# Lipo_Charger_Basic.net
KiCad netlist of a schematic drawn in EAGLE
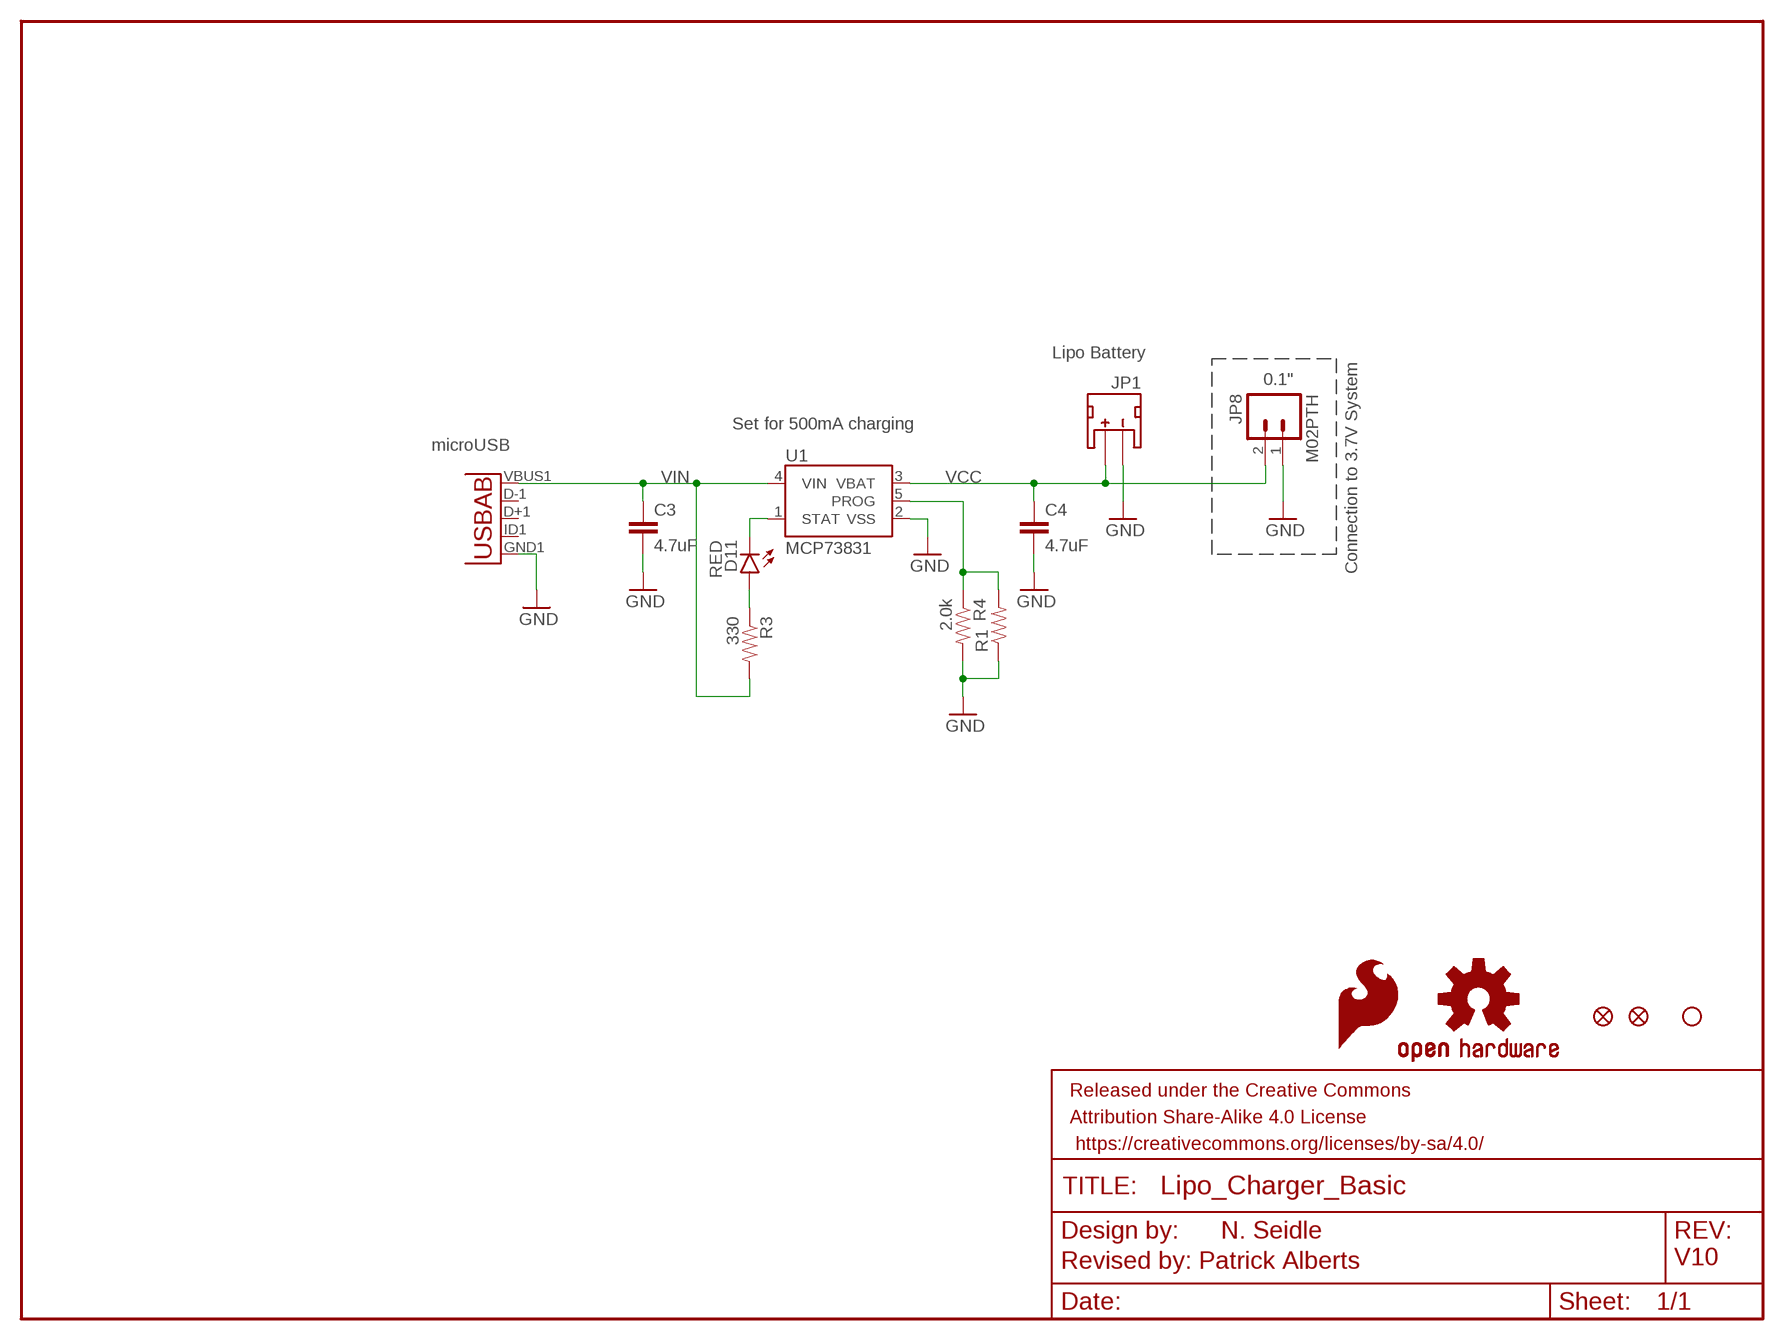
[diagram p0: schematic, sheet 1]

(export (version "E")
  (design (tool "Eeschema 10.0.6"))
  (components
    (comp (ref "C3")
      (value "4.7uF")
      (footprint "eagle-import:0603-CAP")
      (libsource (lib "eagle-import") (part "4.7UF-6.3V-10%(0603)0603"))
    )
    (comp (ref "C4")
      (value "4.7uF")
      (footprint "eagle-import:0603-CAP")
      (libsource (lib "eagle-import") (part "4.7UF-6.3V-10%(0603)0603"))
    )
    (comp (ref "D11")
      (value "RED")
      (footprint "eagle-import:LED-0603")
      (libsource (lib "eagle-import") (part "LED-RED0603"))
    )
    (comp (ref "FRAME1")
      (value "FRAME-LETTER")
      (footprint "eagle-import:CREATIVE_COMMONS")
      (libsource (lib "eagle-import") (part "FRAME-LETTER"))
    )
    (comp (ref "JP1")
      (value "JST")
      (footprint "eagle-import:JST-2-SMD")
      (libsource (lib "eagle-import") (part "JST_2MM_MALE"))
    )
    (comp (ref "JP2")
      (value "STAND-OFF")
      (footprint "eagle-import:STAND-OFF")
      (libsource (lib "eagle-import") (part "STAND-OFF"))
    )
    (comp (ref "JP3")
      (value "FIDUCIAL1X2")
      (footprint "eagle-import:FIDUCIAL-1X2")
      (libsource (lib "eagle-import") (part "FIDUCIAL1X2"))
    )
    (comp (ref "JP4")
      (value "FIDUCIAL1X2")
      (footprint "eagle-import:FIDUCIAL-1X2")
      (libsource (lib "eagle-import") (part "FIDUCIAL1X2"))
    )
    (comp (ref "JP8")
      (value "M02PTH")
      (footprint "eagle-import:1X02")
      (libsource (lib "eagle-import") (part "M02PTH"))
    )
    (comp (ref "JP9")
      (value "Micro USB")
      (footprint "eagle-import:USB-AB-MICRO-SMD_V03")
      (libsource (lib "eagle-import") (part "USB-ABCONN-11794"))
    )
    (comp (ref "LOGO1")
      (value "OSHW-LOGOS")
      (footprint "eagle-import:OSHW-LOGO-S")
      (libsource (lib "eagle-import") (part "OSHW-LOGOS"))
    )
    (comp (ref "LOGO2")
      (value "SFE_LOGO_FLAME.1_INCH")
      (footprint "eagle-import:SFE_LOGO_FLAME_.1")
      (libsource (lib "eagle-import") (part "SFE_LOGO_FLAME.1_INCH"))
    )
    (comp (ref "R1")
      (value "RESISTORPTH-1/4W-VERT-KIT")
      (footprint "eagle-import:AXIAL-0.1EZ")
      (libsource (lib "eagle-import") (part "RESISTORPTH-1/4W-VERT-KIT"))
    )
    (comp (ref "R3")
      (value "330")
      (footprint "eagle-import:0603-RES")
      (libsource (lib "eagle-import") (part "330OHM1/10W1%(0603)"))
    )
    (comp (ref "R4")
      (value "2.0k")
      (footprint "eagle-import:0603-RES")
      (libsource (lib "eagle-import") (part "2.0KOHM1/10W5%(0603)"))
    )
    (comp (ref "U1")
      (value "MCP73831")
      (footprint "eagle-import:SOT23-5")
      (libsource (lib "eagle-import") (part "MCP73831"))
    )
  )
  (nets
    (net (code "1") (name "/VCC") (class "Default")
      (node (ref "C4") (pin "1") (pinfunction "1_1") (pintype "passive"))
      (node (ref "JP1") (pin "2") (pinfunction "+_2") (pintype "bidirectional"))
      (node (ref "JP8") (pin "2") (pinfunction "2_2") (pintype "passive"))
      (node (ref "U1") (pin "3") (pinfunction "VBAT_3") (pintype "power_in"))
    )
    (net (code "2") (name "/VIN") (class "Default")
      (node (ref "C3") (pin "1") (pinfunction "1_1") (pintype "passive"))
      (node (ref "JP9") (pin "VBUS1") (pinfunction "VBUS_VBUS1") (pintype "bidirectional"))
      (node (ref "R3") (pin "2") (pinfunction "2_2") (pintype "passive"))
      (node (ref "U1") (pin "4") (pinfunction "VIN_4") (pintype "power_in"))
    )
    (net (code "3") (name "GND") (class "Default")
      (node (ref "C3") (pin "2") (pinfunction "2_2") (pintype "passive"))
      (node (ref "C4") (pin "2") (pinfunction "2_2") (pintype "passive"))
      (node (ref "JP1") (pin "1") (pinfunction "-_1") (pintype "bidirectional"))
      (node (ref "JP8") (pin "1") (pinfunction "1_1") (pintype "passive"))
      (node (ref "JP9") (pin "GND1") (pinfunction "GND_GND1") (pintype "bidirectional"))
      (node (ref "R1") (pin "P$1") (pinfunction "1_P$1") (pintype "passive"))
      (node (ref "R4") (pin "2") (pinfunction "2_2") (pintype "passive"))
      (node (ref "U1") (pin "2") (pinfunction "VSS_2") (pintype "power_in"))
    )
    (net (code "4") (name "Net-(D11-PadA)") (class "Default")
      (node (ref "D11") (pin "A") (pinfunction "A_A") (pintype "passive"))
      (node (ref "R3") (pin "1") (pinfunction "1_1") (pintype "passive"))
    )
    (net (code "5") (name "Net-(R1-2)") (class "Default")
      (node (ref "R1") (pin "P$2") (pinfunction "2_P$2") (pintype "passive"))
      (node (ref "R4") (pin "1") (pinfunction "1_1") (pintype "passive"))
      (node (ref "U1") (pin "5") (pinfunction "PROG_5") (pintype "input"))
    )
    (net (code "6") (name "Net-(U1-STAT)") (class "Default")
      (node (ref "D11") (pin "C") (pinfunction "C_C") (pintype "passive"))
      (node (ref "U1") (pin "1") (pinfunction "STAT_1") (pintype "output"))
    )
    (net (code "7") (name "unconnected-(JP1-PAD1-PadNC1)") (class "Default")
      (node (ref "JP1") (pin "NC1") (pinfunction "PAD1_NC1") (pintype "bidirectional"))
    )
    (net (code "8") (name "unconnected-(JP1-PAD2-PadNC2)") (class "Default")
      (node (ref "JP1") (pin "NC2") (pinfunction "PAD2_NC2") (pintype "bidirectional"))
    )
    (net (code "9") (name "unconnected-(JP9-D+-PadD+1)") (class "Default")
      (node (ref "JP9") (pin "D+1") (pinfunction "D+_D+1") (pintype "bidirectional"))
    )
    (net (code "10") (name "unconnected-(JP9-D--PadD-1)") (class "Default")
      (node (ref "JP9") (pin "D-1") (pinfunction "D-_D-1") (pintype "bidirectional"))
    )
    (net (code "11") (name "unconnected-(JP9-USBID-PadID1)") (class "Default")
      (node (ref "JP9") (pin "ID1") (pinfunction "USBID_ID1") (pintype "bidirectional"))
    )
  )
)
